# Peripheral2.net
KiCad netlist of a schematic drawn in Altium Designer
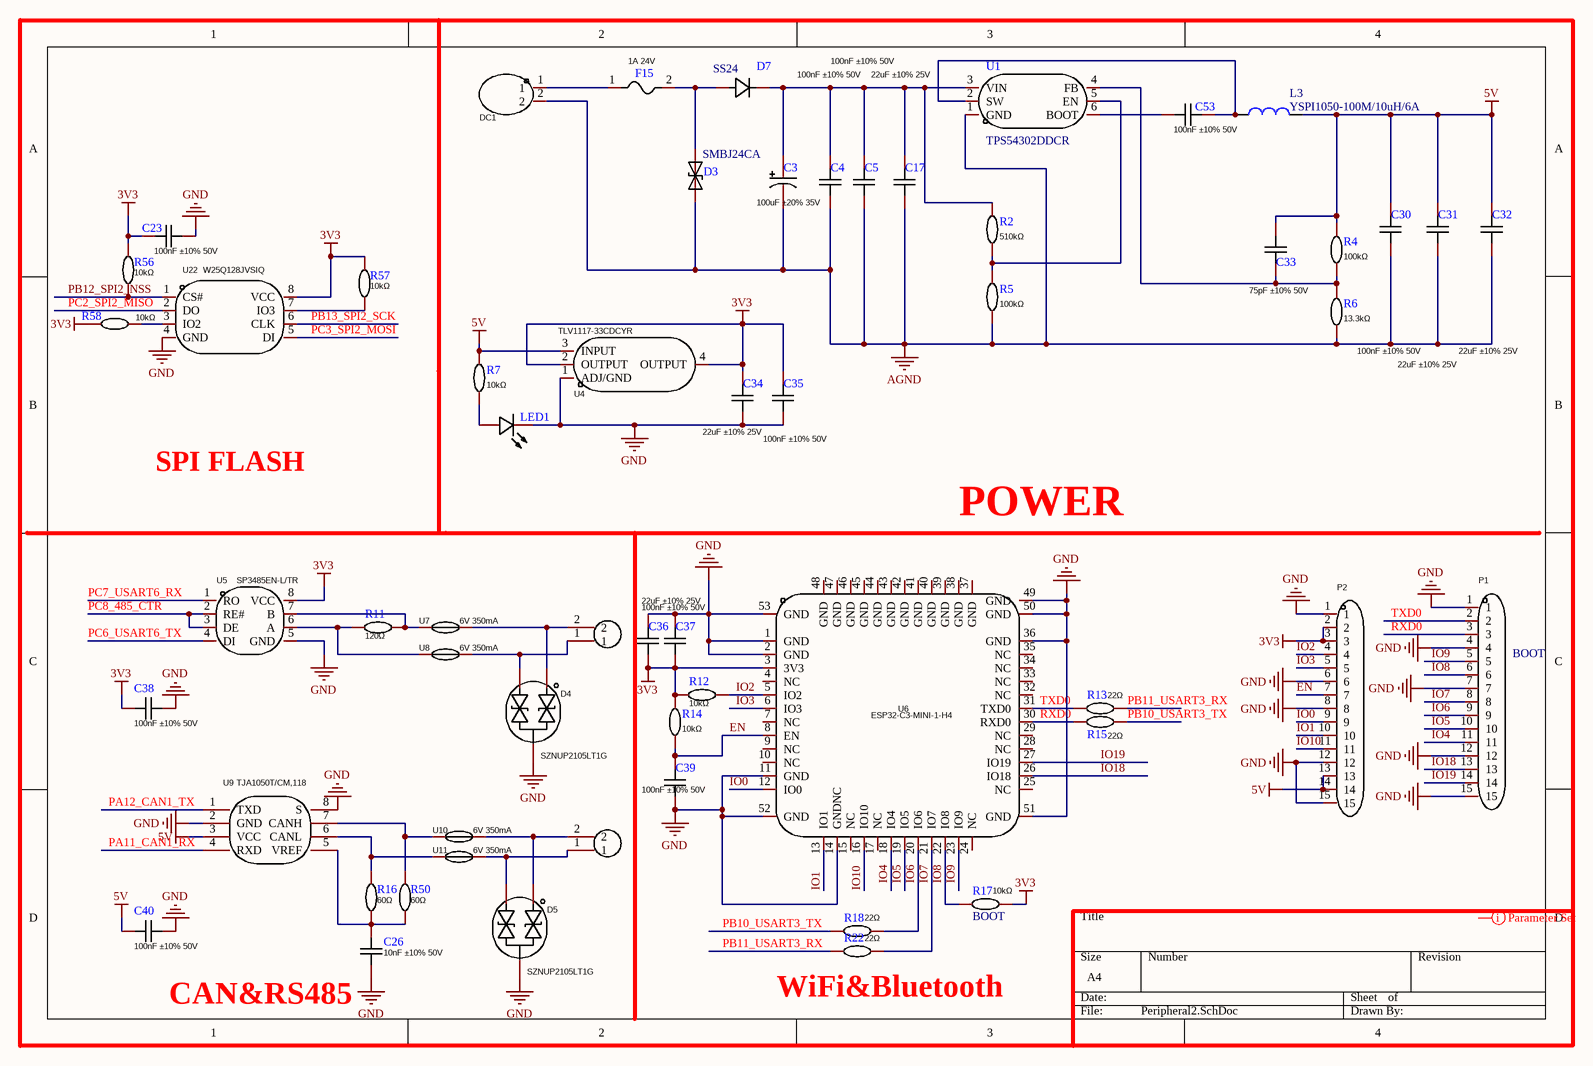
[diagram p0: Peripheral2.SchDoc]

(export (version "E")
  (design (tool "Eeschema 10.0.6"))
  (components
    (comp (ref "C3")
      (value "VES101M1VTR-0607")
      (footprint "CE 6.3*7.7")
      (fields
        (field (name "LCSC PART NAME") "100uF ±20% 35V")
        (field (name "MANUFACTURER") "lelon(立隆)")
        (field (name "TOLERANCE") "±20%")
      )
      (libsource (lib "altium-import") (part "root_0_VES101M1VTR-0607_"))
    )
    (comp (ref "C4")
      (value "CC0603KRX7R9BB104")
      (footprint "C0603")
      (fields
        (field (name "LCSC PART NAME") "100nF ±10% 50V")
        (field (name "MANUFACTURER") "YAGEO(国巨)")
        (field (name "TOLERANCE") "±10%")
      )
      (libsource (lib "altium-import") (part "root_1_CC0603KRX7R9BB104_"))
    )
    (comp (ref "C5")
      (value "CC0603KRX7R9BB104")
      (footprint "C0603")
      (fields
        (field (name "LCSC PART NAME") "100nF ±10% 50V")
        (field (name "MANUFACTURER") "YAGEO(国巨)")
        (field (name "TOLERANCE") "±10%")
      )
      (libsource (lib "altium-import") (part "root_1_CC0603KRX7R9BB104_"))
    )
    (comp (ref "C17")
      (value "CC0603KRX7R9BB104")
      (footprint "C1210")
      (fields
        (field (name "LCSC PART NAME") "22uF ±10% 25V")
        (field (name "MANUFACTURER") "YAGEO(国巨)")
        (field (name "TOLERANCE") "±10%")
      )
      (libsource (lib "altium-import") (part "root_1_CC0603KRX7R9BB104_"))
    )
    (comp (ref "C23")
      (value "CC0603KRX7R9BB104")
      (footprint "C0603")
      (fields
        (field (name "LCSC PART NAME") "100nF ±10% 50V")
        (field (name "MANUFACTURER") "YAGEO(国巨)")
        (field (name "TOLERANCE") "±10%")
      )
      (libsource (lib "altium-import") (part "root_2_CC0603KRX7R9BB104_"))
    )
    (comp (ref "C26")
      (value "CC0603KRX7R9BB104")
      (footprint "C0603")
      (fields
        (field (name "LCSC PART NAME") "10nF ±10% 50V")
        (field (name "MANUFACTURER") "YAGEO(国巨)")
        (field (name "TOLERANCE") "±10%")
      )
      (libsource (lib "altium-import") (part "root_3_CC0603KRX7R9BB104_"))
    )
    (comp (ref "C30")
      (value "CC0603KRX7R9BB104")
      (footprint "C0603")
      (fields
        (field (name "LCSC PART NAME") "100nF ±10% 50V")
        (field (name "MANUFACTURER") "YAGEO(国巨)")
        (field (name "TOLERANCE") "±10%")
      )
      (libsource (lib "altium-import") (part "root_1_CC0603KRX7R9BB104_"))
    )
    (comp (ref "C31")
      (value "CC0603KRX7R9BB104")
      (footprint "C1210")
      (fields
        (field (name "LCSC PART NAME") "22uF ±10% 25V")
        (field (name "MANUFACTURER") "YAGEO(国巨)")
        (field (name "TOLERANCE") "±10%")
      )
      (libsource (lib "altium-import") (part "root_1_CC0603KRX7R9BB104_"))
    )
    (comp (ref "C32")
      (value "CC0603KRX7R9BB104")
      (footprint "C1210")
      (fields
        (field (name "LCSC PART NAME") "22uF ±10% 25V")
        (field (name "MANUFACTURER") "YAGEO(国巨)")
        (field (name "TOLERANCE") "±10%")
      )
      (libsource (lib "altium-import") (part "root_1_CC0603KRX7R9BB104_"))
    )
    (comp (ref "C33")
      (value "CC0603KRX7R9BB104")
      (footprint "C0603")
      (fields
        (field (name "LCSC PART NAME") "75pF ±10% 50V")
        (field (name "MANUFACTURER") "YAGEO(国巨)")
        (field (name "TOLERANCE") "±10%")
      )
      (libsource (lib "altium-import") (part "root_1_CC0603KRX7R9BB104_"))
    )
    (comp (ref "C34")
      (value "CC0603KRX7R9BB104")
      (footprint "C1210")
      (fields
        (field (name "LCSC PART NAME") "22uF ±10% 25V")
        (field (name "MANUFACTURER") "YAGEO(国巨)")
        (field (name "TOLERANCE") "±10%")
      )
      (libsource (lib "altium-import") (part "root_1_CC0603KRX7R9BB104_"))
    )
    (comp (ref "C35")
      (value "CC0603KRX7R9BB104")
      (footprint "C0603")
      (fields
        (field (name "LCSC PART NAME") "100nF ±10% 50V")
        (field (name "MANUFACTURER") "YAGEO(国巨)")
        (field (name "TOLERANCE") "±10%")
      )
      (libsource (lib "altium-import") (part "root_1_CC0603KRX7R9BB104_"))
    )
    (comp (ref "C36")
      (value "CC0603KRX7R9BB104")
      (footprint "C1210")
      (fields
        (field (name "LCSC PART NAME") "22uF ±10% 25V")
        (field (name "MANUFACTURER") "YAGEO(国巨)")
        (field (name "TOLERANCE") "±10%")
      )
      (libsource (lib "altium-import") (part "root_1_CC0603KRX7R9BB104_"))
    )
    (comp (ref "C37")
      (value "CC0603KRX7R9BB104")
      (footprint "C0603")
      (fields
        (field (name "LCSC PART NAME") "100nF ±10% 50V")
        (field (name "MANUFACTURER") "YAGEO(国巨)")
        (field (name "TOLERANCE") "±10%")
      )
      (libsource (lib "altium-import") (part "root_1_CC0603KRX7R9BB104_"))
    )
    (comp (ref "C38")
      (value "CC0603KRX7R9BB104")
      (footprint "C0603")
      (fields
        (field (name "LCSC PART NAME") "100nF ±10% 50V")
        (field (name "MANUFACTURER") "YAGEO(国巨)")
        (field (name "TOLERANCE") "±10%")
      )
      (libsource (lib "altium-import") (part "root_2_CC0603KRX7R9BB104_"))
    )
    (comp (ref "C39")
      (value "CC0603KRX7R9BB104")
      (footprint "C0603")
      (fields
        (field (name "LCSC PART NAME") "100nF ±10% 50V")
        (field (name "MANUFACTURER") "YAGEO(国巨)")
        (field (name "TOLERANCE") "±10%")
      )
      (libsource (lib "altium-import") (part "root_1_CC0603KRX7R9BB104_"))
    )
    (comp (ref "C40")
      (value "CC0603KRX7R9BB104")
      (footprint "C0603")
      (fields
        (field (name "LCSC PART NAME") "100nF ±10% 50V")
        (field (name "MANUFACTURER") "YAGEO(国巨)")
        (field (name "TOLERANCE") "±10%")
      )
      (libsource (lib "altium-import") (part "root_2_CC0603KRX7R9BB104_"))
    )
    (comp (ref "C53")
      (value "CC0603KRX7R9BB104")
      (footprint "C0603")
      (fields
        (field (name "LCSC PART NAME") "100nF ±10% 50V")
        (field (name "MANUFACTURER") "YAGEO(国巨)")
        (field (name "TOLERANCE") "±10%")
      )
      (libsource (lib "altium-import") (part "root_2_CC0603KRX7R9BB104_"))
    )
    (comp (ref "CN1")
      (value "XH-2A_C20079")
      (footprint "XH2.5-2")
      (fields (field (name "MANUFACTURER") "BOOMELE(博穆精密)") (field (name "MANUFACTURER PART") "XH-2A"))
      (libsource (lib "altium-import") (part "root_2_XH-2A_C20079_"))
    )
    (comp (ref "CN2")
      (value "XH-2A_C20079")
      (footprint "XH2.5-2")
      (fields (field (name "MANUFACTURER") "BOOMELE(博穆精密)") (field (name "MANUFACTURER PART") "XH-2A"))
      (libsource (lib "altium-import") (part "root_2_XH-2A_C20079_"))
    )
    (comp (ref "D3")
      (value "SMBJ24CA")
      (footprint "SMB")
      (fields (field (name "MANUFACTURER") "Brightking(君耀电子)"))
      (libsource (lib "altium-import") (part "root_1_SMBJ24CA_C78416_"))
    )
    (comp (ref "D4")
      (value "SZNUP2105LT1G")
      (footprint "SOT-23")
      (fields (field (name "NAME") "SZNUP2105LT1G") (field (name "MANUFACTURER") "onsemi(安森美)"))
      (libsource (lib "altium-import") (part "root_2_SZNUP2105LT1G_"))
    )
    (comp (ref "D5")
      (value "SZNUP2105LT1G")
      (footprint "SOT-23")
      (fields (field (name "NAME") "SZNUP2105LT1G") (field (name "MANUFACTURER") "onsemi(安森美)"))
      (libsource (lib "altium-import") (part "root_2_SZNUP2105LT1G_"))
    )
    (comp (ref "D7")
      (value "SS24")
      (footprint "SMA")
      (fields (field (name "MANUFACTURER") "CJ(江苏长电/长晶)"))
      (libsource (lib "altium-import") (part "root_2_SS24_C2829443_"))
    )
    (comp (ref "DC1")
      (value "A3963WV-2P")
      (footprint "CONN-TH_A3963WV-2P")
      (fields (field (name "MANUFACTURER") "CJT(长江连接器)"))
      (libsource (lib "altium-import") (part "root_0_mirrored_A3963WV-2P_"))
    )
    (comp (ref "F15")
      (value "TLC-NSMD100/24")
      (footprint "F1206")
      (fields (field (name "LCSC PART NAME") "1A 24V") (field (name "MANUFACTURER") "TLC(竞沃)"))
      (libsource (lib "altium-import") (part "root_0_TLC-NSMD100/24_"))
    )
    (comp (ref "L3")
      (value "YSPI1050-100M/10uH/6A")
      (footprint "IND-SMD_L11.5-W10.0_SMMS1040")
      (libsource (lib "*") (part "INDUCTOR"))
    )
    (comp (ref "LED1")
      (value "17-21SYGC/S530-E3/TR8")
      (footprint "LED 0805G")
      (fields (field (name "MANUFACTURER") "EVERLIGHT(亿光)"))
      (libsource (lib "altium-import") (part "root_2_17-21SYGC/S530-E3/TR8_"))
    )
    (comp (ref "P1")
      (value "KH-2.54FH-1X15P-H8.5")
      (footprint "HDR2.54-M-LI-15P")
      (fields (field (name "MANUFACTURER") "kinghelm(金航标)"))
      (libsource (lib "altium-import") (part "root_0_KH-2.54FH-1X15P-H8.5_"))
    )
    (comp (ref "P2")
      (value "KH-2.54FH-1X15P-H8.5")
      (footprint "HDR2.54-M-LI-15P")
      (fields (field (name "MANUFACTURER") "kinghelm(金航标)"))
      (libsource (lib "altium-import") (part "root_0_KH-2.54FH-1X15P-H8.5_"))
    )
    (comp (ref "R2")
      (value "510kΩ")
      (footprint "R0603")
      (fields
        (field (name "MANUFACTURER") "UNI-ROYAL(厚声)")
        (field (name "MANUFACTURER PART") "0603WAF5113T5E")
        (field (name "TOLERANCE") "±1%")
      )
      (libsource (lib "altium-import") (part "root_1_0603WAF5113T5E_"))
    )
    (comp (ref "R4")
      (value "100kΩ")
      (footprint "R0603")
      (fields
        (field (name "MANUFACTURER") "UNI-ROYAL(厚声)")
        (field (name "MANUFACTURER PART") "0603WAF5113T5E")
        (field (name "TOLERANCE") "±1%")
      )
      (libsource (lib "altium-import") (part "root_1_0603WAF5113T5E_"))
    )
    (comp (ref "R5")
      (value "100kΩ")
      (footprint "R0603")
      (fields
        (field (name "MANUFACTURER") "UNI-ROYAL(厚声)")
        (field (name "MANUFACTURER PART") "0603WAF5113T5E")
        (field (name "TOLERANCE") "±1%")
      )
      (libsource (lib "altium-import") (part "root_1_0603WAF5113T5E_"))
    )
    (comp (ref "R6")
      (value "13.3kΩ")
      (footprint "R0603")
      (fields
        (field (name "MANUFACTURER") "UNI-ROYAL(厚声)")
        (field (name "MANUFACTURER PART") "0603WAF5113T5E")
        (field (name "TOLERANCE") "±1%")
      )
      (libsource (lib "altium-import") (part "root_1_0603WAF5113T5E_"))
    )
    (comp (ref "R7")
      (value "10kΩ")
      (footprint "R0603")
      (fields
        (field (name "MANUFACTURER") "UNI-ROYAL(厚声)")
        (field (name "MANUFACTURER PART") "0603WAF5113T5E")
        (field (name "TOLERANCE") "±1%")
      )
      (libsource (lib "altium-import") (part "root_1_0603WAF5113T5E_"))
    )
    (comp (ref "R11")
      (value "120Ω")
      (footprint "R0603")
      (fields
        (field (name "MANUFACTURER") "UNI-ROYAL(厚声)")
        (field (name "MANUFACTURER PART") "0603WAF5113T5E")
        (field (name "TOLERANCE") "±1%")
      )
      (libsource (lib "altium-import") (part "root_2_0603WAF5113T5E_"))
    )
    (comp (ref "R12")
      (value "10kΩ")
      (footprint "R0603")
      (fields
        (field (name "MANUFACTURER") "UNI-ROYAL(厚声)")
        (field (name "MANUFACTURER PART") "0603WAF5113T5E")
        (field (name "TOLERANCE") "±1%")
      )
      (libsource (lib "altium-import") (part "root_2_0603WAF5113T5E_"))
    )
    (comp (ref "R13")
      (value "22Ω")
      (footprint "R0603")
      (fields
        (field (name "MANUFACTURER") "UNI-ROYAL(厚声)")
        (field (name "MANUFACTURER PART") "0603WAF5113T5E")
        (field (name "TOLERANCE") "±1%")
      )
      (libsource (lib "altium-import") (part "root_2_0603WAF5113T5E_"))
    )
    (comp (ref "R14")
      (value "10kΩ")
      (footprint "R0603")
      (fields
        (field (name "MANUFACTURER") "UNI-ROYAL(厚声)")
        (field (name "MANUFACTURER PART") "0603WAF5113T5E")
        (field (name "TOLERANCE") "±1%")
      )
      (libsource (lib "altium-import") (part "root_1_0603WAF5113T5E_"))
    )
    (comp (ref "R15")
      (value "22Ω")
      (footprint "R0603")
      (fields
        (field (name "MANUFACTURER") "UNI-ROYAL(厚声)")
        (field (name "MANUFACTURER PART") "0603WAF5113T5E")
        (field (name "TOLERANCE") "±1%")
      )
      (libsource (lib "altium-import") (part "root_2_0603WAF5113T5E_"))
    )
    (comp (ref "R16")
      (value "60Ω")
      (footprint "R0603")
      (fields
        (field (name "MANUFACTURER") "UNI-ROYAL(厚声)")
        (field (name "MANUFACTURER PART") "0603WAF5113T5E")
        (field (name "TOLERANCE") "±1%")
      )
      (libsource (lib "altium-import") (part "root_3_0603WAF5113T5E_"))
    )
    (comp (ref "R17")
      (value "10kΩ")
      (footprint "R0603")
      (fields
        (field (name "MANUFACTURER") "UNI-ROYAL(厚声)")
        (field (name "MANUFACTURER PART") "0603WAF5113T5E")
        (field (name "TOLERANCE") "±1%")
      )
      (libsource (lib "altium-import") (part "root_2_0603WAF5113T5E_"))
    )
    (comp (ref "R18")
      (value "22Ω")
      (footprint "R0603")
      (fields
        (field (name "MANUFACTURER") "UNI-ROYAL(厚声)")
        (field (name "MANUFACTURER PART") "0603WAF5113T5E")
        (field (name "TOLERANCE") "±1%")
      )
      (libsource (lib "altium-import") (part "root_2_0603WAF5113T5E_"))
    )
    (comp (ref "R22")
      (value "22Ω")
      (footprint "R0603")
      (fields
        (field (name "MANUFACTURER") "UNI-ROYAL(厚声)")
        (field (name "MANUFACTURER PART") "0603WAF5113T5E")
        (field (name "TOLERANCE") "±1%")
      )
      (libsource (lib "altium-import") (part "root_2_0603WAF5113T5E_"))
    )
    (comp (ref "R50")
      (value "60Ω")
      (footprint "R0603")
      (fields
        (field (name "MANUFACTURER") "UNI-ROYAL(厚声)")
        (field (name "MANUFACTURER PART") "0603WAF5113T5E")
        (field (name "TOLERANCE") "±1%")
      )
      (libsource (lib "altium-import") (part "root_3_0603WAF5113T5E_"))
    )
    (comp (ref "R56")
      (value "10kΩ")
      (footprint "R0603")
      (fields
        (field (name "MANUFACTURER") "UNI-ROYAL(厚声)")
        (field (name "MANUFACTURER PART") "0603WAF5113T5E")
        (field (name "TOLERANCE") "±1%")
      )
      (libsource (lib "altium-import") (part "root_3_0603WAF5113T5E_"))
    )
    (comp (ref "R57")
      (value "10kΩ")
      (footprint "R0603")
      (fields
        (field (name "MANUFACTURER") "UNI-ROYAL(厚声)")
        (field (name "MANUFACTURER PART") "0603WAF5113T5E")
        (field (name "TOLERANCE") "±1%")
      )
      (libsource (lib "altium-import") (part "root_3_0603WAF5113T5E_"))
    )
    (comp (ref "R58")
      (value "10kΩ")
      (footprint "R0603")
      (fields
        (field (name "MANUFACTURER") "UNI-ROYAL(厚声)")
        (field (name "MANUFACTURER PART") "0603WAF5113T5E")
        (field (name "TOLERANCE") "±1%")
      )
      (libsource (lib "altium-import") (part "root_2_0603WAF5113T5E_"))
    )
    (comp (ref "U1")
      (value "TPS54302DDCR")
      (footprint "SOT23-6")
      (fields (field (name "MANUFACTURER") "TI(德州仪器)"))
      (libsource (lib "altium-import") (part "root_2_mirrored_TPS54302DDCR_"))
    )
    (comp (ref "U4")
      (value "TLV1117-33CDCYR")
      (footprint "SOT223")
      (fields (field (name "NAME") "TLV1117-33CDCYR") (field (name "MANUFACTURER") "TI(德州仪器)"))
      (libsource (lib "altium-import") (part "root_1_mirrored_TLV1117-33CDCYR_"))
    )
    (comp (ref "U5")
      (value "SP3485EN-L/TR")
      (footprint "SOP8_SP3485")
      (fields (field (name "NAME") "SP3485EN-L/TR") (field (name "MANUFACTURER") "MaxLinear"))
      (libsource (lib "altium-import") (part "root_0_SP3485EN-L/TR_"))
    )
    (comp (ref "U6")
      (value "ESP32-C3-MINI-1-H4")
      (footprint "WIFIM-SMD_ESP32-C3-MINI-1")
      (fields (field (name "NAME") "ESP32-C3-MINI-1-H4") (field (name "MANUFACTURER") "ESPRESSIF(乐鑫)"))
      (libsource (lib "altium-import") (part "root_0_ESP32-C3-MINI-1U-H4_"))
    )
    (comp (ref "U7")
      (value "0603L035YR")
      (footprint "F0603")
      (fields (field (name "LCSC PART NAME") "6V 350mA") (field (name "MANUFACTURER") "Littelfuse(美国力特)"))
      (libsource (lib "altium-import") (part "root_0_0603L035YR_"))
    )
    (comp (ref "U8")
      (value "0603L035YR")
      (footprint "F0603")
      (fields (field (name "LCSC PART NAME") "6V 350mA") (field (name "MANUFACTURER") "Littelfuse(美国力特)"))
      (libsource (lib "altium-import") (part "root_0_0603L035YR_"))
    )
    (comp (ref "U9")
      (value "TJA1050T/CM,118")
      (footprint "SOP8_TJA1050")
      (fields (field (name "NAME") "TJA1050T/CM,118") (field (name "MANUFACTURER") "NXP(恩智浦)"))
      (libsource (lib "altium-import") (part "root_0_TJA1050T/CM,118_"))
    )
    (comp (ref "U10")
      (value "0603L035YR")
      (footprint "F0603")
      (fields (field (name "LCSC PART NAME") "6V 350mA") (field (name "MANUFACTURER") "Littelfuse(美国力特)"))
      (libsource (lib "altium-import") (part "root_0_0603L035YR_"))
    )
    (comp (ref "U11")
      (value "0603L035YR")
      (footprint "F0603")
      (fields (field (name "LCSC PART NAME") "6V 350mA") (field (name "MANUFACTURER") "Littelfuse(美国力特)"))
      (libsource (lib "altium-import") (part "root_0_0603L035YR_"))
    )
    (comp (ref "U22")
      (value "W25Q128JVSIQ")
      (footprint "SOIC8")
      (fields (field (name "NAME") "W25Q128JVSIQ") (field (name "MANUFACTURER") "WINBOND(华邦)"))
      (libsource (lib "altium-import") (part "root_0_W25Q128JVSIQ_"))
    )
  )
  (nets
    (net (code "1") (name "/EN") (class "Default")
      (node (ref "C39") (pin "2") (pinfunction "2_2") (pintype "passive"))
      (node (ref "P2") (pin "7") (pinfunction "7_7") (pintype "passive"))
      (node (ref "R14") (pin "1") (pinfunction "1_1") (pintype "passive"))
      (node (ref "U6") (pin "8") (pinfunction "EN_8") (pintype "passive"))
    )
    (net (code "2") (name "/IO0") (class "Default")
      (node (ref "P2") (pin "9") (pinfunction "9_9") (pintype "passive"))
      (node (ref "U6") (pin "12") (pinfunction "IO0_12") (pintype "passive"))
    )
    (net (code "3") (name "/IO1") (class "Default")
      (node (ref "P2") (pin "10") (pinfunction "10_10") (pintype "passive"))
      (node (ref "U6") (pin "13") (pinfunction "IO1_13") (pintype "passive"))
    )
    (net (code "4") (name "/IO2") (class "Default")
      (node (ref "P2") (pin "4") (pinfunction "4_4") (pintype "passive"))
      (node (ref "R12") (pin "1") (pinfunction "1_1") (pintype "passive"))
      (node (ref "U6") (pin "5") (pinfunction "IO2_5") (pintype "passive"))
    )
    (net (code "5") (name "/IO3") (class "Default")
      (node (ref "P2") (pin "5") (pinfunction "5_5") (pintype "passive"))
      (node (ref "U6") (pin "6") (pinfunction "IO3_6") (pintype "passive"))
    )
    (net (code "6") (name "/IO4") (class "Default")
      (node (ref "P1") (pin "11") (pinfunction "11_11") (pintype "passive"))
      (node (ref "U6") (pin "18") (pinfunction "IO4_18") (pintype "passive"))
    )
    (net (code "7") (name "/IO5") (class "Default")
      (node (ref "P1") (pin "10") (pinfunction "10_10") (pintype "passive"))
      (node (ref "U6") (pin "19") (pinfunction "IO5_19") (pintype "passive"))
    )
    (net (code "8") (name "/IO6") (class "Default")
      (node (ref "P1") (pin "9") (pinfunction "9_9") (pintype "passive"))
      (node (ref "R18") (pin "1") (pinfunction "1_1") (pintype "passive"))
      (node (ref "U6") (pin "20") (pinfunction "IO6_20") (pintype "passive"))
    )
    (net (code "9") (name "/IO7") (class "Default")
      (node (ref "P1") (pin "8") (pinfunction "8_8") (pintype "passive"))
      (node (ref "R22") (pin "1") (pinfunction "1_1") (pintype "passive"))
      (node (ref "U6") (pin "21") (pinfunction "IO7_21") (pintype "passive"))
    )
    (net (code "10") (name "/IO8") (class "Default")
      (node (ref "P1") (pin "6") (pinfunction "6_6") (pintype "passive"))
      (node (ref "R17") (pin "2") (pinfunction "2_2") (pintype "passive"))
      (node (ref "U6") (pin "22") (pinfunction "IO8_22") (pintype "passive"))
    )
    (net (code "11") (name "/IO9") (class "Default")
      (node (ref "P1") (pin "5") (pinfunction "5_5") (pintype "passive"))
      (node (ref "U6") (pin "23") (pinfunction "IO9_23") (pintype "passive"))
    )
    (net (code "12") (name "/IO10") (class "Default")
      (node (ref "P2") (pin "11") (pinfunction "11_11") (pintype "passive"))
      (node (ref "U6") (pin "16") (pinfunction "IO10_16") (pintype "passive"))
    )
    (net (code "13") (name "/IO18") (class "Default")
      (node (ref "P1") (pin "13") (pinfunction "13_13") (pintype "passive"))
      (node (ref "U6") (pin "26") (pinfunction "IO18_26") (pintype "passive"))
    )
    (net (code "14") (name "/IO19") (class "Default")
      (node (ref "P1") (pin "14") (pinfunction "14_14") (pintype "passive"))
      (node (ref "U6") (pin "27") (pinfunction "IO19_27") (pintype "passive"))
    )
    (net (code "15") (name "/PA11_CAN1_RX") (class "Default")
      (node (ref "U9") (pin "4") (pinfunction "RXD_4") (pintype "passive"))
    )
    (net (code "16") (name "/PA12_CAN1_TX") (class "Default")
      (node (ref "U9") (pin "1") (pinfunction "TXD_1") (pintype "passive"))
    )
    (net (code "17") (name "/PB10_USART3_TX") (class "Default")
      (node (ref "R15") (pin "1") (pinfunction "1_1") (pintype "passive"))
      (node (ref "R18") (pin "2") (pinfunction "2_2") (pintype "passive"))
    )
    (net (code "18") (name "/PB11_USART3_RX") (class "Default")
      (node (ref "R13") (pin "1") (pinfunction "1_1") (pintype "passive"))
      (node (ref "R22") (pin "2") (pinfunction "2_2") (pintype "passive"))
    )
    (net (code "19") (name "/PB12_SPI2_NSS") (class "Default")
      (node (ref "R56") (pin "2") (pinfunction "2_2") (pintype "passive"))
      (node (ref "U22") (pin "1") (pinfunction "CS#_1") (pintype "passive"))
    )
    (net (code "20") (name "/PB13_SPI2_SCK") (class "Default")
      (node (ref "U22") (pin "6") (pinfunction "CLK_6") (pintype "passive"))
    )
    (net (code "21") (name "/PC2_SPI2_MISO") (class "Default")
      (node (ref "U22") (pin "2") (pinfunction "DO_2") (pintype "passive"))
    )
    (net (code "22") (name "/PC3_SPI2_MOSI") (class "Default")
      (node (ref "U22") (pin "5") (pinfunction "DI_5") (pintype "passive"))
    )
    (net (code "23") (name "/PC6_USART6_TX") (class "Default")
      (node (ref "U5") (pin "4") (pinfunction "DI_4") (pintype "passive"))
    )
    (net (code "24") (name "/PC7_USART6_RX") (class "Default")
      (node (ref "U5") (pin "1") (pinfunction "RO_1") (pintype "passive"))
    )
    (net (code "25") (name "/PC8_485_CTR") (class "Default")
      (node (ref "U5") (pin "2") (pinfunction "RE#_2") (pintype "passive"))
      (node (ref "U5") (pin "3") (pinfunction "DE_3") (pintype "passive"))
    )
    (net (code "26") (name "/RXD0") (class "Default")
      (node (ref "P1") (pin "3") (pinfunction "3_3") (pintype "passive"))
      (node (ref "R15") (pin "2") (pinfunction "2_2") (pintype "passive"))
      (node (ref "U6") (pin "30") (pinfunction "RXD0_30") (pintype "passive"))
    )
    (net (code "27") (name "/TXD0") (class "Default")
      (node (ref "P1") (pin "2") (pinfunction "2_2") (pintype "passive"))
      (node (ref "R13") (pin "2") (pinfunction "2_2") (pintype "passive"))
      (node (ref "U6") (pin "31") (pinfunction "TXD0_31") (pintype "passive"))
    )
    (net (code "28") (name "3V3") (class "Default")
      (node (ref "C23") (pin "2") (pinfunction "2_2") (pintype "passive"))
      (node (ref "C34") (pin "2") (pinfunction "2_2") (pintype "passive"))
      (node (ref "C35") (pin "2") (pinfunction "2_2") (pintype "passive"))
      (node (ref "C36") (pin "1") (pinfunction "1_1") (pintype "passive"))
      (node (ref "C37") (pin "1") (pinfunction "1_1") (pintype "passive"))
      (node (ref "C38") (pin "2") (pinfunction "2_2") (pintype "passive"))
      (node (ref "P2") (pin "2") (pinfunction "2_2") (pintype "passive"))
      (node (ref "P2") (pin "3") (pinfunction "3_3") (pintype "passive"))
      (node (ref "R12") (pin "2") (pinfunction "2_2") (pintype "passive"))
      (node (ref "R14") (pin "2") (pinfunction "2_2") (pintype "passive"))
      (node (ref "R17") (pin "1") (pinfunction "1_1") (pintype "passive"))
      (node (ref "R56") (pin "1") (pinfunction "1_1") (pintype "passive"))
      (node (ref "R57") (pin "1") (pinfunction "1_1") (pintype "passive"))
      (node (ref "R58") (pin "2") (pinfunction "2_2") (pintype "passive"))
      (node (ref "U22") (pin "8") (pinfunction "VCC_8") (pintype "passive"))
      (node (ref "U4") (pin "2") (pinfunction "OUTPUT_2") (pintype "passive"))
      (node (ref "U4") (pin "4") (pinfunction "OUTPUT_4") (pintype "passive"))
      (node (ref "U5") (pin "8") (pinfunction "VCC_8") (pintype "passive"))
      (node (ref "U6") (pin "3") (pinfunction "3V3_3") (pintype "passive"))
    )
    (net (code "29") (name "5V") (class "Default")
      (node (ref "C30") (pin "2") (pinfunction "2_2") (pintype "passive"))
      (node (ref "C31") (pin "2") (pinfunction "2_2") (pintype "passive"))
      (node (ref "C32") (pin "2") (pinfunction "2_2") (pintype "passive"))
      (node (ref "C33") (pin "2") (pinfunction "2_2") (pintype "passive"))
      (node (ref "C40") (pin "2") (pinfunction "2_2") (pintype "passive"))
      (node (ref "L3") (pin "2") (pinfunction "2_2") (pintype "passive"))
      (node (ref "P2") (pin "13") (pinfunction "13_13") (pintype "passive"))
      (node (ref "P2") (pin "14") (pinfunction "14_14") (pintype "passive"))
      (node (ref "R4") (pin "2") (pinfunction "2_2") (pintype "passive"))
      (node (ref "R7") (pin "2") (pinfunction "2_2") (pintype "passive"))
      (node (ref "U4") (pin "3") (pinfunction "INPUT_3") (pintype "passive"))
      (node (ref "U9") (pin "3") (pinfunction "VCC_3") (pintype "passive"))
    )
    (net (code "30") (name "AGND") (class "Default")
      (node (ref "C17") (pin "1") (pinfunction "1_1") (pintype "passive"))
      (node (ref "C3") (pin "2") (pinfunction "2_2") (pintype "passive"))
      (node (ref "C30") (pin "1") (pinfunction "1_1") (pintype "passive"))
      (node (ref "C31") (pin "1") (pinfunction "1_1") (pintype "passive"))
      (node (ref "C32") (pin "1") (pinfunction "1_1") (pintype "passive"))
      (node (ref "C4") (pin "1") (pinfunction "1_1") (pintype "passive"))
      (node (ref "C5") (pin "1") (pinfunction "1_1") (pintype "passive"))
      (node (ref "D3") (pin "2") (pinfunction "A_2") (pintype "passive"))
      (node (ref "DC1") (pin "2") (pinfunction "2_2") (pintype "passive"))
      (node (ref "R5") (pin "1") (pinfunction "1_1") (pintype "passive"))
      (node (ref "R6") (pin "1") (pinfunction "1_1") (pintype "passive"))
      (node (ref "U1") (pin "1") (pinfunction "GND_1") (pintype "passive"))
    )
    (net (code "31") (name "GND") (class "Default")
      (node (ref "C23") (pin "1") (pinfunction "1_1") (pintype "passive"))
      (node (ref "C26") (pin "2") (pinfunction "2_2") (pintype "passive"))
      (node (ref "C34") (pin "1") (pinfunction "1_1") (pintype "passive"))
      (node (ref "C35") (pin "1") (pinfunction "1_1") (pintype "passive"))
      (node (ref "C36") (pin "2") (pinfunction "2_2") (pintype "passive"))
      (node (ref "C37") (pin "2") (pinfunction "2_2") (pintype "passive"))
      (node (ref "C38") (pin "1") (pinfunction "1_1") (pintype "passive"))
      (node (ref "C39") (pin "1") (pinfunction "1_1") (pintype "passive"))
      (node (ref "C40") (pin "1") (pinfunction "1_1") (pintype "passive"))
      (node (ref "D4") (pin "3") (pinfunction "3_3") (pintype "passive"))
      (node (ref "D5") (pin "3") (pinfunction "3_3") (pintype "passive"))
      (node (ref "LED1") (pin "1") (pinfunction "K_1") (pintype "passive"))
      (node (ref "P1") (pin "1") (pinfunction "1_1") (pintype "passive"))
      (node (ref "P1") (pin "12") (pinfunction "12_12") (pintype "passive"))
      (node (ref "P1") (pin "15") (pinfunction "15_15") (pintype "passive"))
      (node (ref "P1") (pin "4") (pinfunction "4_4") (pintype "passive"))
      (node (ref "P1") (pin "7") (pinfunction "7_7") (pintype "passive"))
      (node (ref "P2") (pin "1") (pinfunction "1_1") (pintype "passive"))
      (node (ref "P2") (pin "12") (pinfunction "12_12") (pintype "passive"))
      (node (ref "P2") (pin "15") (pinfunction "15_15") (pintype "passive"))
      (node (ref "P2") (pin "6") (pinfunction "6_6") (pintype "passive"))
      (node (ref "P2") (pin "8") (pinfunction "8_8") (pintype "passive"))
      (node (ref "U22") (pin "4") (pinfunction "GND_4") (pintype "passive"))
      (node (ref "U4") (pin "1") (pinfunction "ADJ/GND_1") (pintype "passive"))
      (node (ref "U5") (pin "5") (pinfunction "GND_5") (pintype "passive"))
      (node (ref "U6") (pin "1") (pinfunction "GND_1") (pintype "passive"))
      (node (ref "U6") (pin "11") (pinfunction "GND_11") (pintype "passive"))
      (node (ref "U6") (pin "14") (pinfunction "GNDNC_14") (pintype "passive"))
      (node (ref "U6") (pin "2") (pinfunction "GND_2") (pintype "passive"))
      (node (ref "U6") (pin "36") (pinfunction "GND_36") (pintype "passive"))
      (node (ref "U6") (pin "49") (pinfunction "GND_49") (pintype "passive"))
      (node (ref "U6") (pin "50") (pinfunction "GND_50") (pintype "passive"))
      (node (ref "U6") (pin "51") (pinfunction "GND_51") (pintype "passive"))
      (node (ref "U6") (pin "52") (pinfunction "GND_52") (pintype "passive"))
      (node (ref "U6") (pin "53") (pinfunction "GND_53") (pintype "passive"))
      (node (ref "U9") (pin "2") (pinfunction "GND_2") (pintype "passive"))
      (node (ref "U9") (pin "8") (pinfunction "S_8") (pintype "passive"))
    )
    (net (code "32") (name "Net-(CN1-Pad1)") (class "Default")
      (node (ref "CN1") (pin "1") (pinfunction "1_1") (pintype "passive"))
      (node (ref "D4") (pin "2") (pinfunction "2_2") (pintype "passive"))
      (node (ref "U8") (pin "2") (pinfunction "2_2") (pintype "passive"))
    )
    (net (code "33") (name "Net-(CN1-Pad2)") (class "Default")
      (node (ref "CN1") (pin "2") (pinfunction "2_2") (pintype "passive"))
      (node (ref "D4") (pin "1") (pinfunction "1_1") (pintype "passive"))
      (node (ref "U7") (pin "2") (pinfunction "2_2") (pintype "passive"))
    )
    (net (code "34") (name "Net-(CN2-Pad1)") (class "Default")
      (node (ref "CN2") (pin "1") (pinfunction "1_1") (pintype "passive"))
      (node (ref "D5") (pin "2") (pinfunction "2_2") (pintype "passive"))
      (node (ref "U11") (pin "2") (pinfunction "2_2") (pintype "passive"))
    )
    (net (code "35") (name "Net-(CN2-Pad2)") (class "Default")
      (node (ref "CN2") (pin "2") (pinfunction "2_2") (pintype "passive"))
      (node (ref "D5") (pin "1") (pinfunction "1_1") (pintype "passive"))
      (node (ref "U10") (pin "2") (pinfunction "2_2") (pintype "passive"))
    )
    (net (code "36") (name "Net-(D3-K)") (class "Default")
      (node (ref "D3") (pin "1") (pinfunction "K_1") (pintype "passive"))
      (node (ref "D7") (pin "2") (pinfunction "A_2") (pintype "passive"))
      (node (ref "F15") (pin "2") (pinfunction "2_2") (pintype "passive"))
    )
    (net (code "37") (name "Net-(D7-K)") (class "Default")
      (node (ref "C17") (pin "2") (pinfunction "2_2") (pintype "passive"))
      (node (ref "C3") (pin "1") (pinfunction "1_1") (pintype "passive"))
      (node (ref "C4") (pin "2") (pinfunction "2_2") (pintype "passive"))
      (node (ref "C5") (pin "2") (pinfunction "2_2") (pintype "passive"))
      (node (ref "D7") (pin "1") (pinfunction "K_1") (pintype "passive"))
      (node (ref "R2") (pin "2") (pinfunction "2_2") (pintype "passive"))
      (node (ref "U1") (pin "3") (pinfunction "VIN_3") (pintype "passive"))
    )
    (net (code "38") (name "Net-(DC1-Pad1)") (class "Default")
      (node (ref "DC1") (pin "1") (pinfunction "1_1") (pintype "passive"))
      (node (ref "F15") (pin "1") (pinfunction "1_1") (pintype "passive"))
    )
    (net (code "39") (name "Net-(LED1-A)") (class "Default")
      (node (ref "LED1") (pin "2") (pinfunction "A_2") (pintype "passive"))
      (node (ref "R7") (pin "1") (pinfunction "1_1") (pintype "passive"))
    )
    (net (code "40") (name "Net-(U1-BOOT)") (class "Default")
      (node (ref "C53") (pin "2") (pinfunction "2_2") (pintype "passive"))
      (node (ref "U1") (pin "6") (pinfunction "BOOT_6") (pintype "passive"))
    )
    (net (code "41") (name "Net-(U1-EN)") (class "Default")
      (node (ref "R2") (pin "1") (pinfunction "1_1") (pintype "passive"))
      (node (ref "R5") (pin "2") (pinfunction "2_2") (pintype "passive"))
      (node (ref "U1") (pin "5") (pinfunction "EN_5") (pintype "passive"))
    )
    (net (code "42") (name "Net-(U1-FB)") (class "Default")
      (node (ref "C33") (pin "1") (pinfunction "1_1") (pintype "passive"))
      (node (ref "R4") (pin "1") (pinfunction "1_1") (pintype "passive"))
      (node (ref "R6") (pin "2") (pinfunction "2_2") (pintype "passive"))
      (node (ref "U1") (pin "4") (pinfunction "FB_4") (pintype "passive"))
    )
    (net (code "43") (name "Net-(U1-SW)") (class "Default")
      (node (ref "C53") (pin "1") (pinfunction "1_1") (pintype "passive"))
      (node (ref "L3") (pin "1") (pinfunction "1_1") (pintype "passive"))
      (node (ref "U1") (pin "2") (pinfunction "SW_2") (pintype "passive"))
    )
    (net (code "44") (name "Net-(U5-A)") (class "Default")
      (node (ref "R11") (pin "2") (pinfunction "2_2") (pintype "passive"))
      (node (ref "U5") (pin "6") (pinfunction "A_6") (pintype "passive"))
      (node (ref "U8") (pin "1") (pinfunction "1_1") (pintype "passive"))
    )
    (net (code "45") (name "Net-(U5-B)") (class "Default")
      (node (ref "R11") (pin "1") (pinfunction "1_1") (pintype "passive"))
      (node (ref "U5") (pin "7") (pinfunction "B_7") (pintype "passive"))
      (node (ref "U7") (pin "1") (pinfunction "1_1") (pintype "passive"))
    )
    (net (code "46") (name "Net-(U9-CANH)") (class "Default")
      (node (ref "R50") (pin "1") (pinfunction "1_1") (pintype "passive"))
      (node (ref "U10") (pin "1") (pinfunction "1_1") (pintype "passive"))
      (node (ref "U9") (pin "7") (pinfunction "CANH_7") (pintype "passive"))
    )
    (net (code "47") (name "Net-(U9-CANL)") (class "Default")
      (node (ref "R16") (pin "1") (pinfunction "1_1") (pintype "passive"))
      (node (ref "U11") (pin "1") (pinfunction "1_1") (pintype "passive"))
      (node (ref "U9") (pin "6") (pinfunction "CANL_6") (pintype "passive"))
    )
    (net (code "48") (name "Net-(U9-VREF)") (class "Default")
      (node (ref "C26") (pin "1") (pinfunction "1_1") (pintype "passive"))
      (node (ref "R16") (pin "2") (pinfunction "2_2") (pintype "passive"))
      (node (ref "R50") (pin "2") (pinfunction "2_2") (pintype "passive"))
      (node (ref "U9") (pin "5") (pinfunction "VREF_5") (pintype "passive"))
    )
    (net (code "49") (name "Net-(U22-IO2)") (class "Default")
      (node (ref "R58") (pin "1") (pinfunction "1_1") (pintype "passive"))
      (node (ref "U22") (pin "3") (pinfunction "IO2_3") (pintype "passive"))
    )
    (net (code "50") (name "Net-(U22-IO3)") (class "Default")
      (node (ref "R57") (pin "2") (pinfunction "2_2") (pintype "passive"))
      (node (ref "U22") (pin "7") (pinfunction "IO3_7") (pintype "passive"))
    )
    (net (code "51") (name "unconnected-(U6-GND-Pad37)") (class "Default")
      (node (ref "U6") (pin "37") (pinfunction "GND_37") (pintype "passive"))
    )
    (net (code "52") (name "unconnected-(U6-GND-Pad38)") (class "Default")
      (node (ref "U6") (pin "38") (pinfunction "GND_38") (pintype "passive"))
    )
    (net (code "53") (name "unconnected-(U6-GND-Pad39)") (class "Default")
      (node (ref "U6") (pin "39") (pinfunction "GND_39") (pintype "passive"))
    )
    (net (code "54") (name "unconnected-(U6-GND-Pad40)") (class "Default")
      (node (ref "U6") (pin "40") (pinfunction "GND_40") (pintype "passive"))
    )
    (net (code "55") (name "unconnected-(U6-GND-Pad41)") (class "Default")
      (node (ref "U6") (pin "41") (pinfunction "GND_41") (pintype "passive"))
    )
    (net (code "56") (name "unconnected-(U6-GND-Pad42)") (class "Default")
      (node (ref "U6") (pin "42") (pinfunction "GND_42") (pintype "passive"))
    )
    (net (code "57") (name "unconnected-(U6-GND-Pad43)") (class "Default")
      (node (ref "U6") (pin "43") (pinfunction "GND_43") (pintype "passive"))
    )
    (net (code "58") (name "unconnected-(U6-GND-Pad44)") (class "Default")
      (node (ref "U6") (pin "44") (pinfunction "GND_44") (pintype "passive"))
    )
    (net (code "59") (name "unconnected-(U6-GND-Pad45)") (class "Default")
      (node (ref "U6") (pin "45") (pinfunction "GND_45") (pintype "passive"))
    )
    (net (code "60") (name "unconnected-(U6-GND-Pad46)") (class "Default")
      (node (ref "U6") (pin "46") (pinfunction "GND_46") (pintype "passive"))
    )
    (net (code "61") (name "unconnected-(U6-GND-Pad47)") (class "Default")
      (node (ref "U6") (pin "47") (pinfunction "GND_47") (pintype "passive"))
    )
    (net (code "62") (name "unconnected-(U6-GND-Pad48)") (class "Default")
      (node (ref "U6") (pin "48") (pinfunction "GND_48") (pintype "passive"))
    )
    (net (code "63") (name "unconnected-(U6-NC-Pad4)") (class "Default")
      (node (ref "U6") (pin "4") (pinfunction "NC_4") (pintype "passive"))
    )
    (net (code "64") (name "unconnected-(U6-NC-Pad7)") (class "Default")
      (node (ref "U6") (pin "7") (pinfunction "NC_7") (pintype "passive"))
    )
    (net (code "65") (name "unconnected-(U6-NC-Pad9)") (class "Default")
      (node (ref "U6") (pin "9") (pinfunction "NC_9") (pintype "passive"))
    )
    (net (code "66") (name "unconnected-(U6-NC-Pad10)") (class "Default")
      (node (ref "U6") (pin "10") (pinfunction "NC_10") (pintype "passive"))
    )
    (net (code "67") (name "unconnected-(U6-NC-Pad15)") (class "Default")
      (node (ref "U6") (pin "15") (pinfunction "NC_15") (pintype "passive"))
    )
    (net (code "68") (name "unconnected-(U6-NC-Pad17)") (class "Default")
      (node (ref "U6") (pin "17") (pinfunction "NC_17") (pintype "passive"))
    )
    (net (code "69") (name "unconnected-(U6-NC-Pad24)") (class "Default")
      (node (ref "U6") (pin "24") (pinfunction "NC_24") (pintype "passive"))
    )
    (net (code "70") (name "unconnected-(U6-NC-Pad25)") (class "Default")
      (node (ref "U6") (pin "25") (pinfunction "NC_25") (pintype "passive"))
    )
    (net (code "71") (name "unconnected-(U6-NC-Pad28)") (class "Default")
      (node (ref "U6") (pin "28") (pinfunction "NC_28") (pintype "passive"))
    )
    (net (code "72") (name "unconnected-(U6-NC-Pad29)") (class "Default")
      (node (ref "U6") (pin "29") (pinfunction "NC_29") (pintype "passive"))
    )
    (net (code "73") (name "unconnected-(U6-NC-Pad32)") (class "Default")
      (node (ref "U6") (pin "32") (pinfunction "NC_32") (pintype "passive"))
    )
    (net (code "74") (name "unconnected-(U6-NC-Pad33)") (class "Default")
      (node (ref "U6") (pin "33") (pinfunction "NC_33") (pintype "passive"))
    )
    (net (code "75") (name "unconnected-(U6-NC-Pad34)") (class "Default")
      (node (ref "U6") (pin "34") (pinfunction "NC_34") (pintype "passive"))
    )
    (net (code "76") (name "unconnected-(U6-NC-Pad35)") (class "Default")
      (node (ref "U6") (pin "35") (pinfunction "NC_35") (pintype "passive"))
    )
  )
)
